# Punktschweis_pulser.net
KiCad netlist of a schematic drawn in EAGLE
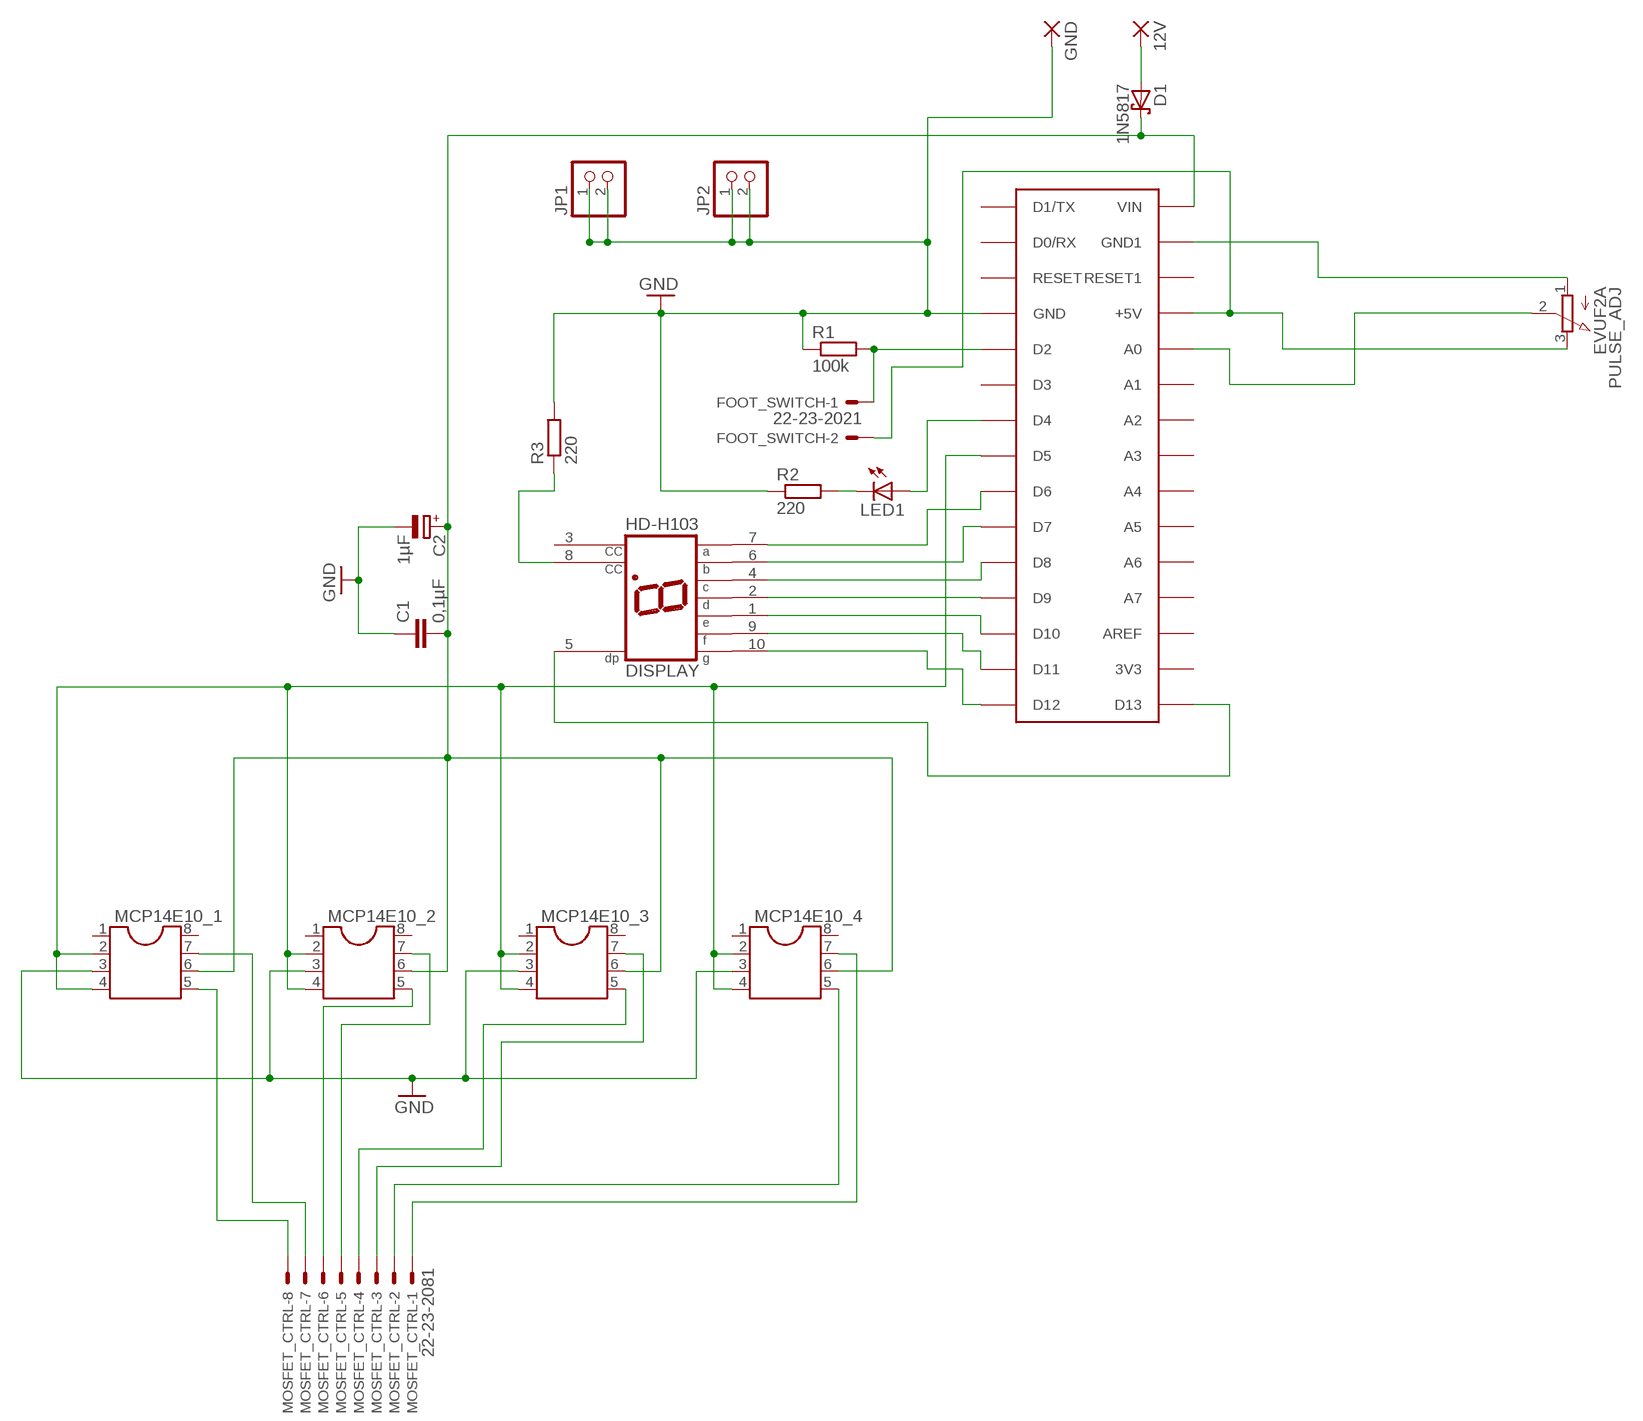
[diagram p0: schematic, sheet 1]

(export (version "E")
  (design (tool "Eeschema 10.0.6"))
  (components
    (comp (ref "12V")
      (value "2,54/0,8")
      (footprint "eagle-import:2,54_0,8")
      (libsource (lib "eagle-import") (part "2,54/0,8"))
    )
    (comp (ref "C1")
      (value "0,1µF")
      (footprint "eagle-import:C2.5-4")
      (libsource (lib "eagle-import") (part "C2.5/4"))
    )
    (comp (ref "C2")
      (value "1µF")
      (footprint "eagle-import:E2-5")
      (libsource (lib "eagle-import") (part "CPOL-EUE2-5"))
    )
    (comp (ref "D1")
      (value "1N5817")
      (footprint "eagle-import:DO41-10")
      (libsource (lib "eagle-import") (part "SCHOTTKY-DIODEDO41"))
    )
    (comp (ref "DISPLAY")
      (value "HD-H103")
      (footprint "eagle-import:HDSP-M")
      (libsource (lib "eagle-import") (part "HD-H103"))
    )
    (comp (ref "FOOT_SWITCH")
      (value "22-23-2021")
      (footprint "eagle-import:22-23-2021")
      (fields (field (name "MF") "MOLEX"))
      (libsource (lib "eagle-import") (part "22-23-2021"))
    )
    (comp (ref "GND")
      (value "2,54/0,8")
      (footprint "eagle-import:2,54_0,8")
      (libsource (lib "eagle-import") (part "2,54/0,8"))
    )
    (comp (ref "JP1")
      (value "PINHD-1X2")
      (footprint "eagle-import:1X02")
      (libsource (lib "eagle-import") (part "PINHD-1X2"))
    )
    (comp (ref "JP2")
      (value "PINHD-1X2")
      (footprint "eagle-import:1X02")
      (libsource (lib "eagle-import") (part "PINHD-1X2"))
    )
    (comp (ref "LED1")
      (value "LED5MM")
      (footprint "eagle-import:LED5MM")
      (libsource (lib "eagle-import") (part "LED5MM"))
    )
    (comp (ref "MCP14E10_1")
      (value "DIL8")
      (footprint "eagle-import:DIL08")
      (libsource (lib "eagle-import") (part "DIL8"))
    )
    (comp (ref "MCP14E10_2")
      (value "DIL8")
      (footprint "eagle-import:DIL08")
      (libsource (lib "eagle-import") (part "DIL8"))
    )
    (comp (ref "MCP14E10_3")
      (value "DIL8")
      (footprint "eagle-import:DIL08")
      (libsource (lib "eagle-import") (part "DIL8"))
    )
    (comp (ref "MCP14E10_4")
      (value "DIL8")
      (footprint "eagle-import:DIL08")
      (libsource (lib "eagle-import") (part "DIL8"))
    )
    (comp (ref "MOSFET_CTRL")
      (value "22-23-2081")
      (footprint "eagle-import:22-23-2081")
      (fields (field (name "MF") "MOLEX"))
      (libsource (lib "eagle-import") (part "22-23-2081"))
    )
    (comp (ref "PULSE_ADJ")
      (value "EVUF2A")
      (footprint "eagle-import:EVUF")
      (libsource (lib "eagle-import") (part "EVUAF2"))
    )
    (comp (ref "R1")
      (value "100k")
      (footprint "eagle-import:0207_10")
      (libsource (lib "eagle-import") (part "R-EU_0207/10"))
    )
    (comp (ref "R2")
      (value "220")
      (footprint "eagle-import:0207_10")
      (libsource (lib "eagle-import") (part "R-EU_0207/10"))
    )
    (comp (ref "R3")
      (value "220")
      (footprint "eagle-import:0207_10")
      (libsource (lib "eagle-import") (part "R-EU_0207/10"))
    )
    (comp (ref "U$1")
      (value "ARDUINONANO")
      (footprint "eagle-import:PDIP-32")
      (libsource (lib "eagle-import") (part "ARDUINONANO"))
    )
  )
  (nets
    (net (code "1") (name "GND") (class "Default")
      (node (ref "C1") (pin "1") (pinfunction "1_1") (pintype "passive"))
      (node (ref "C2") (pin "-") (pinfunction "-_-") (pintype "passive"))
      (node (ref "GND") (pin "1") (pinfunction "P_1") (pintype "passive"))
      (node (ref "JP1") (pin "1") (pinfunction "1_1") (pintype "passive"))
      (node (ref "JP1") (pin "2") (pinfunction "2_2") (pintype "passive"))
      (node (ref "JP2") (pin "1") (pinfunction "1_1") (pintype "passive"))
      (node (ref "JP2") (pin "2") (pinfunction "2_2") (pintype "passive"))
      (node (ref "MCP14E10_1") (pin "3") (pinfunction "3_3") (pintype "passive"))
      (node (ref "MCP14E10_2") (pin "3") (pinfunction "3_3") (pintype "passive"))
      (node (ref "MCP14E10_3") (pin "3") (pinfunction "3_3") (pintype "passive"))
      (node (ref "MCP14E10_4") (pin "3") (pinfunction "3_3") (pintype "passive"))
      (node (ref "R1") (pin "1") (pinfunction "1_1") (pintype "passive"))
      (node (ref "R2") (pin "1") (pinfunction "1_1") (pintype "passive"))
      (node (ref "R3") (pin "2") (pinfunction "2_2") (pintype "passive"))
      (node (ref "U$1") (pin "GND") (pinfunction "GND_GND") (pintype "bidirectional"))
    )
    (net (code "2") (name "Net-(12V-P)") (class "Default")
      (node (ref "12V") (pin "1") (pinfunction "P_1") (pintype "passive"))
      (node (ref "D1") (pin "A") (pinfunction "A_A") (pintype "passive"))
    )
    (net (code "3") (name "Net-(C1-Pad2)") (class "Default")
      (node (ref "C1") (pin "2") (pinfunction "2_2") (pintype "passive"))
      (node (ref "C2") (pin "+") (pinfunction "+_+") (pintype "passive"))
      (node (ref "D1") (pin "C") (pinfunction "C_C") (pintype "passive"))
      (node (ref "MCP14E10_1") (pin "6") (pinfunction "6_6") (pintype "passive"))
      (node (ref "MCP14E10_2") (pin "6") (pinfunction "6_6") (pintype "passive"))
      (node (ref "MCP14E10_3") (pin "6") (pinfunction "6_6") (pintype "passive"))
      (node (ref "MCP14E10_4") (pin "6") (pinfunction "6_6") (pintype "passive"))
      (node (ref "U$1") (pin "VIN") (pinfunction "VIN_VIN") (pintype "bidirectional"))
    )
    (net (code "4") (name "Net-(DISPLAY-A)") (class "Default")
      (node (ref "DISPLAY") (pin "7") (pinfunction "A_7") (pintype "passive"))
      (node (ref "U$1") (pin "D6") (pinfunction "D6_D6") (pintype "bidirectional"))
    )
    (net (code "5") (name "Net-(DISPLAY-B)") (class "Default")
      (node (ref "DISPLAY") (pin "6") (pinfunction "B_6") (pintype "passive"))
      (node (ref "U$1") (pin "D7") (pinfunction "D7_D7") (pintype "bidirectional"))
    )
    (net (code "6") (name "Net-(DISPLAY-C)") (class "Default")
      (node (ref "DISPLAY") (pin "4") (pinfunction "C_4") (pintype "passive"))
      (node (ref "U$1") (pin "D8") (pinfunction "D8_D8") (pintype "bidirectional"))
    )
    (net (code "7") (name "Net-(DISPLAY-CC-Pad8)") (class "Default")
      (node (ref "DISPLAY") (pin "8") (pinfunction "CC_8") (pintype "passive"))
      (node (ref "R3") (pin "1") (pinfunction "1_1") (pintype "passive"))
    )
    (net (code "8") (name "Net-(DISPLAY-D)") (class "Default")
      (node (ref "DISPLAY") (pin "2") (pinfunction "D_2") (pintype "passive"))
      (node (ref "U$1") (pin "D9") (pinfunction "D9_D9") (pintype "bidirectional"))
    )
    (net (code "9") (name "Net-(DISPLAY-DP)") (class "Default")
      (node (ref "DISPLAY") (pin "5") (pinfunction "DP_5") (pintype "passive"))
      (node (ref "U$1") (pin "D13") (pinfunction "D13_D13") (pintype "bidirectional"))
    )
    (net (code "10") (name "Net-(DISPLAY-E)") (class "Default")
      (node (ref "DISPLAY") (pin "1") (pinfunction "E_1") (pintype "passive"))
      (node (ref "U$1") (pin "D10") (pinfunction "D10_D10") (pintype "bidirectional"))
    )
    (net (code "11") (name "Net-(DISPLAY-F)") (class "Default")
      (node (ref "DISPLAY") (pin "9") (pinfunction "F_9") (pintype "passive"))
      (node (ref "U$1") (pin "D11") (pinfunction "D11_D11") (pintype "bidirectional"))
    )
    (net (code "12") (name "Net-(DISPLAY-G)") (class "Default")
      (node (ref "DISPLAY") (pin "10") (pinfunction "G_10") (pintype "passive"))
      (node (ref "U$1") (pin "D12") (pinfunction "D12_D12") (pintype "bidirectional"))
    )
    (net (code "13") (name "Net-(FOOT_SWITCHA-S)") (class "Default")
      (node (ref "FOOT_SWITCH") (pin "1") (pinfunction "S_1") (pintype "passive"))
      (node (ref "R1") (pin "2") (pinfunction "2_2") (pintype "passive"))
      (node (ref "U$1") (pin "D2") (pinfunction "D2_D2") (pintype "bidirectional"))
    )
    (net (code "14") (name "Net-(FOOT_SWITCHB-S)") (class "Default")
      (node (ref "FOOT_SWITCH") (pin "2") (pinfunction "S_2") (pintype "passive"))
      (node (ref "PULSE_ADJ") (pin "3") (pinfunction "E_3") (pintype "passive"))
      (node (ref "U$1") (pin "+5V") (pinfunction "+5V_+5V") (pintype "bidirectional"))
    )
    (net (code "15") (name "Net-(LED1-C)") (class "Default")
      (node (ref "LED1") (pin "K") (pinfunction "C_K") (pintype "passive"))
      (node (ref "R2") (pin "2") (pinfunction "2_2") (pintype "passive"))
    )
    (net (code "16") (name "Net-(LED1-PadA)") (class "Default")
      (node (ref "LED1") (pin "A") (pinfunction "A_A") (pintype "passive"))
      (node (ref "U$1") (pin "D4") (pinfunction "D4_D4") (pintype "bidirectional"))
    )
    (net (code "17") (name "Net-(MCP14E10_1-Pad2)") (class "Default")
      (node (ref "MCP14E10_1") (pin "2") (pinfunction "2_2") (pintype "passive"))
      (node (ref "MCP14E10_1") (pin "4") (pinfunction "4_4") (pintype "passive"))
      (node (ref "MCP14E10_2") (pin "2") (pinfunction "2_2") (pintype "passive"))
      (node (ref "MCP14E10_2") (pin "4") (pinfunction "4_4") (pintype "passive"))
      (node (ref "MCP14E10_3") (pin "2") (pinfunction "2_2") (pintype "passive"))
      (node (ref "MCP14E10_3") (pin "4") (pinfunction "4_4") (pintype "passive"))
      (node (ref "MCP14E10_4") (pin "2") (pinfunction "2_2") (pintype "passive"))
      (node (ref "MCP14E10_4") (pin "4") (pinfunction "4_4") (pintype "passive"))
      (node (ref "U$1") (pin "D5") (pinfunction "D5_D5") (pintype "bidirectional"))
    )
    (net (code "18") (name "Net-(MOSFET_CTRLA-S)") (class "Default")
      (node (ref "MCP14E10_4") (pin "7") (pinfunction "7_7") (pintype "passive"))
      (node (ref "MOSFET_CTRL") (pin "1") (pinfunction "S_1") (pintype "passive"))
    )
    (net (code "19") (name "Net-(MOSFET_CTRLB-S)") (class "Default")
      (node (ref "MCP14E10_4") (pin "5") (pinfunction "5_5") (pintype "passive"))
      (node (ref "MOSFET_CTRL") (pin "2") (pinfunction "S_2") (pintype "passive"))
    )
    (net (code "20") (name "Net-(MOSFET_CTRLC-S)") (class "Default")
      (node (ref "MCP14E10_3") (pin "7") (pinfunction "7_7") (pintype "passive"))
      (node (ref "MOSFET_CTRL") (pin "3") (pinfunction "S_3") (pintype "passive"))
    )
    (net (code "21") (name "Net-(MOSFET_CTRLD-S)") (class "Default")
      (node (ref "MCP14E10_3") (pin "5") (pinfunction "5_5") (pintype "passive"))
      (node (ref "MOSFET_CTRL") (pin "4") (pinfunction "S_4") (pintype "passive"))
    )
    (net (code "22") (name "Net-(MOSFET_CTRLE-S)") (class "Default")
      (node (ref "MCP14E10_2") (pin "7") (pinfunction "7_7") (pintype "passive"))
      (node (ref "MOSFET_CTRL") (pin "5") (pinfunction "S_5") (pintype "passive"))
    )
    (net (code "23") (name "Net-(MOSFET_CTRLF-S)") (class "Default")
      (node (ref "MCP14E10_2") (pin "5") (pinfunction "5_5") (pintype "passive"))
      (node (ref "MOSFET_CTRL") (pin "6") (pinfunction "S_6") (pintype "passive"))
    )
    (net (code "24") (name "Net-(MOSFET_CTRLG-S)") (class "Default")
      (node (ref "MCP14E10_1") (pin "7") (pinfunction "7_7") (pintype "passive"))
      (node (ref "MOSFET_CTRL") (pin "7") (pinfunction "S_7") (pintype "passive"))
    )
    (net (code "25") (name "Net-(MOSFET_CTRLH-S)") (class "Default")
      (node (ref "MCP14E10_1") (pin "5") (pinfunction "5_5") (pintype "passive"))
      (node (ref "MOSFET_CTRL") (pin "8") (pinfunction "S_8") (pintype "passive"))
    )
    (net (code "26") (name "Net-(PULSE_ADJ-A)") (class "Default")
      (node (ref "PULSE_ADJ") (pin "1") (pinfunction "A_1") (pintype "passive"))
      (node (ref "U$1") (pin "GND1") (pinfunction "GND1_GND1") (pintype "bidirectional"))
    )
    (net (code "27") (name "Net-(PULSE_ADJ-S)") (class "Default")
      (node (ref "PULSE_ADJ") (pin "2") (pinfunction "S_2") (pintype "passive"))
      (node (ref "U$1") (pin "A0") (pinfunction "A0_A0") (pintype "bidirectional"))
    )
    (net (code "28") (name "unconnected-(DISPLAY-CC-Pad3)") (class "Default")
      (node (ref "DISPLAY") (pin "3") (pinfunction "CC_3") (pintype "passive"))
    )
    (net (code "29") (name "unconnected-(MCP14E10_1-Pad1)") (class "Default")
      (node (ref "MCP14E10_1") (pin "1") (pinfunction "1_1") (pintype "passive"))
    )
    (net (code "30") (name "unconnected-(MCP14E10_1-Pad8)") (class "Default")
      (node (ref "MCP14E10_1") (pin "8") (pinfunction "8_8") (pintype "passive"))
    )
    (net (code "31") (name "unconnected-(MCP14E10_2-Pad1)") (class "Default")
      (node (ref "MCP14E10_2") (pin "1") (pinfunction "1_1") (pintype "passive"))
    )
    (net (code "32") (name "unconnected-(MCP14E10_2-Pad8)") (class "Default")
      (node (ref "MCP14E10_2") (pin "8") (pinfunction "8_8") (pintype "passive"))
    )
    (net (code "33") (name "unconnected-(MCP14E10_3-Pad1)") (class "Default")
      (node (ref "MCP14E10_3") (pin "1") (pinfunction "1_1") (pintype "passive"))
    )
    (net (code "34") (name "unconnected-(MCP14E10_3-Pad8)") (class "Default")
      (node (ref "MCP14E10_3") (pin "8") (pinfunction "8_8") (pintype "passive"))
    )
    (net (code "35") (name "unconnected-(MCP14E10_4-Pad1)") (class "Default")
      (node (ref "MCP14E10_4") (pin "1") (pinfunction "1_1") (pintype "passive"))
    )
    (net (code "36") (name "unconnected-(MCP14E10_4-Pad8)") (class "Default")
      (node (ref "MCP14E10_4") (pin "8") (pinfunction "8_8") (pintype "passive"))
    )
    (net (code "37") (name "unconnected-(U$1-Pad3V3)") (class "Default")
      (node (ref "U$1") (pin "3V3") (pinfunction "3V3_3V3") (pintype "bidirectional"))
    )
    (net (code "38") (name "unconnected-(U$1-PadA1)") (class "Default")
      (node (ref "U$1") (pin "A1") (pinfunction "A1_A1") (pintype "bidirectional"))
    )
    (net (code "39") (name "unconnected-(U$1-PadA2)") (class "Default")
      (node (ref "U$1") (pin "A2") (pinfunction "A2_A2") (pintype "bidirectional"))
    )
    (net (code "40") (name "unconnected-(U$1-PadA3)") (class "Default")
      (node (ref "U$1") (pin "A3") (pinfunction "A3_A3") (pintype "bidirectional"))
    )
    (net (code "41") (name "unconnected-(U$1-PadA4)") (class "Default")
      (node (ref "U$1") (pin "A4") (pinfunction "A4_A4") (pintype "bidirectional"))
    )
    (net (code "42") (name "unconnected-(U$1-PadA5)") (class "Default")
      (node (ref "U$1") (pin "A5") (pinfunction "A5_A5") (pintype "bidirectional"))
    )
    (net (code "43") (name "unconnected-(U$1-PadA6)") (class "Default")
      (node (ref "U$1") (pin "A6") (pinfunction "A6_A6") (pintype "bidirectional"))
    )
    (net (code "44") (name "unconnected-(U$1-PadA7)") (class "Default")
      (node (ref "U$1") (pin "A7") (pinfunction "A7_A7") (pintype "bidirectional"))
    )
    (net (code "45") (name "unconnected-(U$1-PadAREF)") (class "Default")
      (node (ref "U$1") (pin "AREF") (pinfunction "AREF_AREF") (pintype "bidirectional"))
    )
    (net (code "46") (name "unconnected-(U$1-PadD0{slash}RX)") (class "Default")
      (node (ref "U$1") (pin "D0/RX") (pinfunction "D0/RX_D0/RX") (pintype "bidirectional"))
    )
    (net (code "47") (name "unconnected-(U$1-PadD1{slash}TX)") (class "Default")
      (node (ref "U$1") (pin "D1/TX") (pinfunction "D1/TX_D1/TX") (pintype "bidirectional"))
    )
    (net (code "48") (name "unconnected-(U$1-PadD3)") (class "Default")
      (node (ref "U$1") (pin "D3") (pinfunction "D3_D3") (pintype "bidirectional"))
    )
    (net (code "49") (name "unconnected-(U$1-PadRESET)") (class "Default")
      (node (ref "U$1") (pin "RESET") (pinfunction "RESET_RESET") (pintype "bidirectional"))
    )
    (net (code "50") (name "unconnected-(U$1-PadRESET1)") (class "Default")
      (node (ref "U$1") (pin "RESET1") (pinfunction "RESET1_RESET1") (pintype "bidirectional"))
    )
  )
)
